# avrcp_m_1_2.net
KiCad netlist of a schematic drawn in EAGLE
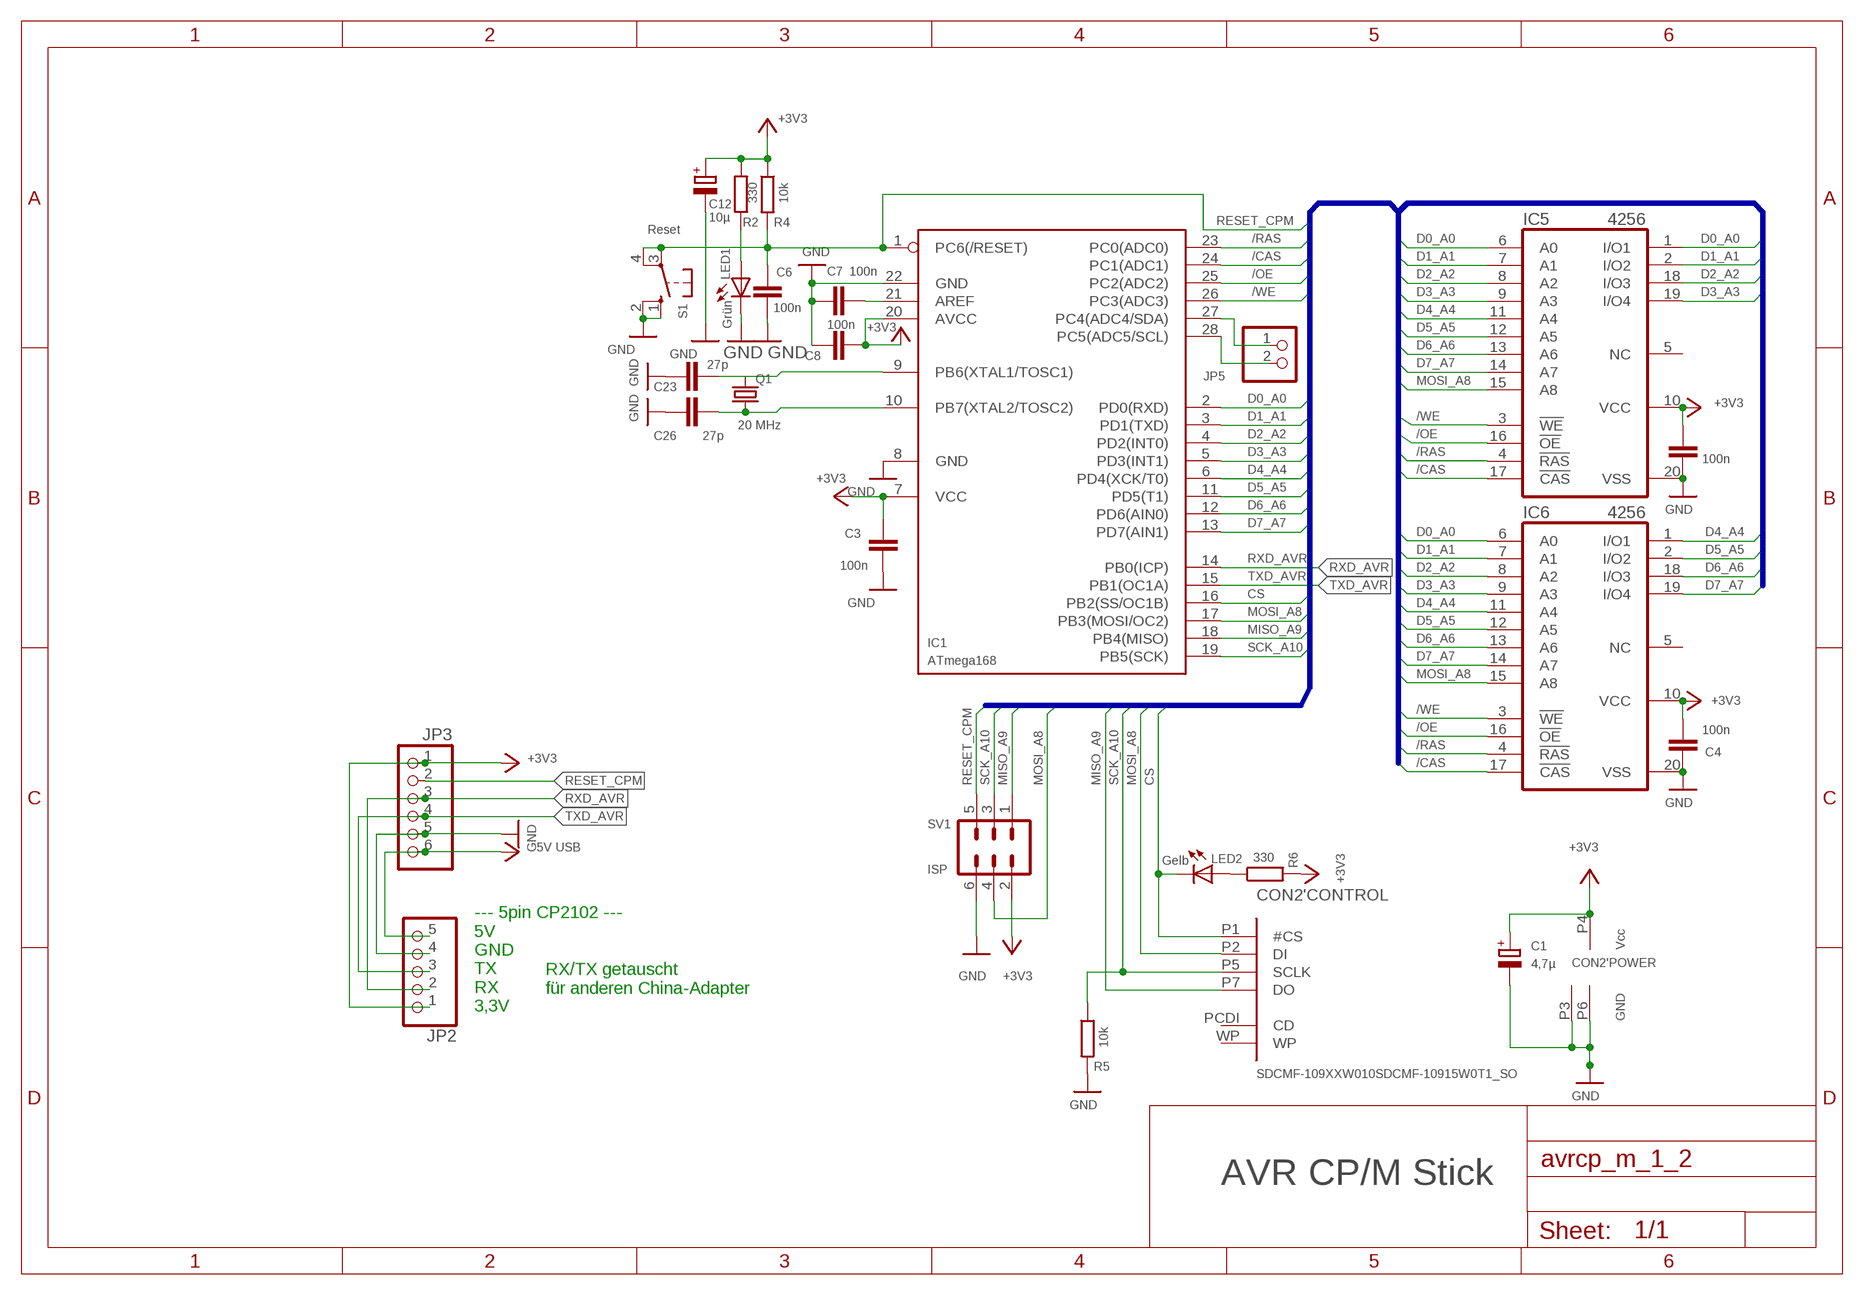
[diagram p0: schematic, sheet 1]

(export (version "E")
  (design (tool "Eeschema 10.0.6"))
  (components
    (comp (ref "C1")
      (value "4,7µ")
      (footprint "eagle-import:E2-4")
      (libsource (lib "eagle-import") (part "CPOL-EUE2-4"))
    )
    (comp (ref "C3")
      (value "100n")
      (footprint "eagle-import:C025-024X044")
      (libsource (lib "eagle-import") (part "C-EU025-024X044"))
    )
    (comp (ref "C4")
      (value "100n")
      (footprint "eagle-import:C025-024X044")
      (libsource (lib "eagle-import") (part "C-EU025-024X044"))
    )
    (comp (ref "C6")
      (value "100n")
      (footprint "eagle-import:C025-024X044")
      (libsource (lib "eagle-import") (part "C-EU025-024X044"))
    )
    (comp (ref "C7")
      (value "100n")
      (footprint "eagle-import:C025-024X044")
      (libsource (lib "eagle-import") (part "C-EU025-024X044"))
    )
    (comp (ref "C8")
      (value "100n")
      (footprint "eagle-import:C025-024X044")
      (libsource (lib "eagle-import") (part "C-EU025-024X044"))
    )
    (comp (ref "C12")
      (value "10µ")
      (footprint "eagle-import:E2-4")
      (libsource (lib "eagle-import") (part "CPOL-EUE2-4"))
    )
    (comp (ref "C15")
      (value "100n")
      (footprint "eagle-import:C025-024X044")
      (libsource (lib "eagle-import") (part "C-EU025-024X044"))
    )
    (comp (ref "C23")
      (value "27p")
      (footprint "eagle-import:C025-024X044")
      (libsource (lib "eagle-import") (part "C-EU025-024X044"))
    )
    (comp (ref "C26")
      (value "27p")
      (footprint "eagle-import:C025-024X044")
      (libsource (lib "eagle-import") (part "C-EU025-024X044"))
    )
    (comp (ref "CON2")
      (value "SDCMF-109XXW010SDCMF-10915W0T1_SO")
      (footprint "eagle-import:SDCMF-10915W0T1")
      (libsource (lib "eagle-import") (part "SDCMF-109XXW010SDCMF-10915W0T1_SO"))
    )
    (comp (ref "IC1")
      (value "ATmega168")
      (footprint "eagle-import:DIL28-3")
      (libsource (lib "eagle-import") (part "MEGA8-P"))
    )
    (comp (ref "IC5")
      (value "4256")
      (footprint "eagle-import:DIL20")
      (libsource (lib "eagle-import") (part "514256ALP"))
    )
    (comp (ref "IC6")
      (value "4256")
      (footprint "eagle-import:DIL20")
      (libsource (lib "eagle-import") (part "514256ALP"))
    )
    (comp (ref "JP2")
      (value "PINHD-1X5")
      (footprint "eagle-import:1X05")
      (libsource (lib "eagle-import") (part "PINHD-1X5"))
    )
    (comp (ref "JP3")
      (value "PINHD-1X6")
      (footprint "eagle-import:1X06")
      (libsource (lib "eagle-import") (part "PINHD-1X6"))
    )
    (comp (ref "JP5")
      (value "PINHD-1X2")
      (footprint "eagle-import:1X02")
      (libsource (lib "eagle-import") (part "PINHD-1X2"))
    )
    (comp (ref "LED1")
      (value "Grün")
      (footprint "eagle-import:LED3MM")
      (libsource (lib "eagle-import") (part "LED3MM"))
    )
    (comp (ref "LED2")
      (value "Gelb")
      (footprint "eagle-import:LED3MM")
      (libsource (lib "eagle-import") (part "LED3MM"))
    )
    (comp (ref "Q1")
      (value "20 MHz")
      (footprint "eagle-import:HC49_S")
      (libsource (lib "eagle-import") (part "CRYSTALHC49S"))
    )
    (comp (ref "R2")
      (value "330")
      (footprint "eagle-import:0207_7")
      (libsource (lib "eagle-import") (part "R-EU_0207/7"))
    )
    (comp (ref "R4")
      (value "10k")
      (footprint "eagle-import:0207_7")
      (libsource (lib "eagle-import") (part "R-EU_0207/7"))
    )
    (comp (ref "R5")
      (value "10k")
      (footprint "eagle-import:0204_7")
      (libsource (lib "eagle-import") (part "R-EU_0204/7"))
    )
    (comp (ref "R6")
      (value "330")
      (footprint "eagle-import:0204_7")
      (libsource (lib "eagle-import") (part "R-EU_0204/7"))
    )
    (comp (ref "S1")
      (value "Reset")
      (footprint "eagle-import:B3F-10XX")
      (libsource (lib "eagle-import") (part "10-XX"))
    )
    (comp (ref "SV1")
      (value "ISP")
      (footprint "eagle-import:ML6")
      (libsource (lib "eagle-import") (part "ML6"))
    )
  )
  (nets
    (net (code "1") (name "+3V3") (class "Default")
      (node (ref "C1") (pin "+") (pinfunction "+_+") (pintype "passive"))
      (node (ref "C12") (pin "+") (pinfunction "+_+") (pintype "passive"))
      (node (ref "C15") (pin "2") (pinfunction "2_2") (pintype "passive"))
      (node (ref "C3") (pin "1") (pinfunction "1_1") (pintype "passive"))
      (node (ref "C4") (pin "2") (pinfunction "2_2") (pintype "passive"))
      (node (ref "C8") (pin "1") (pinfunction "1_1") (pintype "passive"))
      (node (ref "CON2") (pin "P4") (pinfunction "VCC_P4") (pintype "power_in"))
      (node (ref "IC1") (pin "20") (pinfunction "AVCC_20") (pintype "power_in"))
      (node (ref "IC1") (pin "7") (pinfunction "VCC_7") (pintype "power_in"))
      (node (ref "IC5") (pin "10") (pinfunction "VCC_10") (pintype "power_in"))
      (node (ref "IC6") (pin "10") (pinfunction "VCC_10") (pintype "power_in"))
      (node (ref "JP2") (pin "1") (pinfunction "1_1") (pintype "passive"))
      (node (ref "JP3") (pin "1") (pinfunction "1_1") (pintype "passive"))
      (node (ref "R2") (pin "2") (pinfunction "2_2") (pintype "passive"))
      (node (ref "R4") (pin "1") (pinfunction "1_1") (pintype "passive"))
      (node (ref "R6") (pin "2") (pinfunction "2_2") (pintype "passive"))
      (node (ref "SV1") (pin "2") (pinfunction "2_2") (pintype "passive"))
    )
    (net (code "2") (name "/CS") (class "Default")
      (node (ref "CON2") (pin "P1") (pinfunction "#CS_P1") (pintype "input"))
      (node (ref "IC1") (pin "16") (pinfunction "PB2(SS/OC1B)_16") (pintype "bidirectional"))
      (node (ref "LED2") (pin "K") (pinfunction "C_K") (pintype "passive"))
    )
    (net (code "3") (name "/D0_A0") (class "Default")
      (node (ref "IC1") (pin "2") (pinfunction "PD0(RXD)_2") (pintype "bidirectional"))
      (node (ref "IC5") (pin "1") (pinfunction "I/O1_1") (pintype "bidirectional"))
      (node (ref "IC5") (pin "6") (pinfunction "A0_6") (pintype "input"))
      (node (ref "IC6") (pin "6") (pinfunction "A0_6") (pintype "input"))
    )
    (net (code "4") (name "/D1_A1") (class "Default")
      (node (ref "IC1") (pin "3") (pinfunction "PD1(TXD)_3") (pintype "bidirectional"))
      (node (ref "IC5") (pin "2") (pinfunction "I/O2_2") (pintype "bidirectional"))
      (node (ref "IC5") (pin "7") (pinfunction "A1_7") (pintype "input"))
      (node (ref "IC6") (pin "7") (pinfunction "A1_7") (pintype "input"))
    )
    (net (code "5") (name "/D2_A2") (class "Default")
      (node (ref "IC1") (pin "4") (pinfunction "PD2(INT0)_4") (pintype "bidirectional"))
      (node (ref "IC5") (pin "18") (pinfunction "I/O3_18") (pintype "bidirectional"))
      (node (ref "IC5") (pin "8") (pinfunction "A2_8") (pintype "input"))
      (node (ref "IC6") (pin "8") (pinfunction "A2_8") (pintype "input"))
    )
    (net (code "6") (name "/D3_A3") (class "Default")
      (node (ref "IC1") (pin "5") (pinfunction "PD3(INT1)_5") (pintype "bidirectional"))
      (node (ref "IC5") (pin "19") (pinfunction "I/O4_19") (pintype "bidirectional"))
      (node (ref "IC5") (pin "9") (pinfunction "A3_9") (pintype "input"))
      (node (ref "IC6") (pin "9") (pinfunction "A3_9") (pintype "input"))
    )
    (net (code "7") (name "/D4_A4") (class "Default")
      (node (ref "IC1") (pin "6") (pinfunction "PD4(XCK/T0)_6") (pintype "bidirectional"))
      (node (ref "IC5") (pin "11") (pinfunction "A4_11") (pintype "input"))
      (node (ref "IC6") (pin "1") (pinfunction "I/O1_1") (pintype "bidirectional"))
      (node (ref "IC6") (pin "11") (pinfunction "A4_11") (pintype "input"))
    )
    (net (code "8") (name "/D5_A5") (class "Default")
      (node (ref "IC1") (pin "11") (pinfunction "PD5(T1)_11") (pintype "bidirectional"))
      (node (ref "IC5") (pin "12") (pinfunction "A5_12") (pintype "input"))
      (node (ref "IC6") (pin "12") (pinfunction "A5_12") (pintype "input"))
      (node (ref "IC6") (pin "2") (pinfunction "I/O2_2") (pintype "bidirectional"))
    )
    (net (code "9") (name "/D6_A6") (class "Default")
      (node (ref "IC1") (pin "12") (pinfunction "PD6(AIN0)_12") (pintype "bidirectional"))
      (node (ref "IC5") (pin "13") (pinfunction "A6_13") (pintype "input"))
      (node (ref "IC6") (pin "13") (pinfunction "A6_13") (pintype "input"))
      (node (ref "IC6") (pin "18") (pinfunction "I/O3_18") (pintype "bidirectional"))
    )
    (net (code "10") (name "/D7_A7") (class "Default")
      (node (ref "IC1") (pin "13") (pinfunction "PD7(AIN1)_13") (pintype "bidirectional"))
      (node (ref "IC5") (pin "14") (pinfunction "A7_14") (pintype "input"))
      (node (ref "IC6") (pin "14") (pinfunction "A7_14") (pintype "input"))
      (node (ref "IC6") (pin "19") (pinfunction "I/O4_19") (pintype "bidirectional"))
    )
    (net (code "11") (name "/MISO_A9") (class "Default")
      (node (ref "CON2") (pin "P7") (pinfunction "DO_P7") (pintype "output"))
      (node (ref "IC1") (pin "18") (pinfunction "PB4(MISO)_18") (pintype "bidirectional"))
      (node (ref "SV1") (pin "1") (pinfunction "1_1") (pintype "passive"))
    )
    (net (code "12") (name "/MOSI_A8") (class "Default")
      (node (ref "CON2") (pin "P2") (pinfunction "DI_P2") (pintype "input"))
      (node (ref "IC1") (pin "17") (pinfunction "PB3(MOSI/OC2)_17") (pintype "bidirectional"))
      (node (ref "IC5") (pin "15") (pinfunction "A8_15") (pintype "input"))
      (node (ref "IC6") (pin "15") (pinfunction "A8_15") (pintype "input"))
      (node (ref "SV1") (pin "4") (pinfunction "4_4") (pintype "passive"))
    )
    (net (code "13") (name "/SCK_A10") (class "Default")
      (node (ref "CON2") (pin "P5") (pinfunction "SCLK_P5") (pintype "input"))
      (node (ref "IC1") (pin "19") (pinfunction "PB5(SCK)_19") (pintype "bidirectional"))
      (node (ref "R5") (pin "1") (pinfunction "1_1") (pintype "passive"))
      (node (ref "SV1") (pin "3") (pinfunction "3_3") (pintype "passive"))
    )
    (net (code "14") (name "/{slash}CAS") (class "Default")
      (node (ref "IC1") (pin "24") (pinfunction "PC1(ADC1)_24") (pintype "bidirectional"))
      (node (ref "IC5") (pin "17") (pinfunction "~{CAS}_17") (pintype "input"))
      (node (ref "IC6") (pin "17") (pinfunction "~{CAS}_17") (pintype "input"))
    )
    (net (code "15") (name "/{slash}OE") (class "Default")
      (node (ref "IC1") (pin "25") (pinfunction "PC2(ADC2)_25") (pintype "bidirectional"))
      (node (ref "IC5") (pin "16") (pinfunction "~{OE}_16") (pintype "input"))
      (node (ref "IC6") (pin "16") (pinfunction "~{OE}_16") (pintype "input"))
    )
    (net (code "16") (name "/{slash}RAS") (class "Default")
      (node (ref "IC1") (pin "23") (pinfunction "PC0(ADC0)_23") (pintype "bidirectional"))
      (node (ref "IC5") (pin "4") (pinfunction "~{RAS}_4") (pintype "input"))
      (node (ref "IC6") (pin "4") (pinfunction "~{RAS}_4") (pintype "input"))
    )
    (net (code "17") (name "/{slash}WE") (class "Default")
      (node (ref "IC1") (pin "26") (pinfunction "PC3(ADC3)_26") (pintype "bidirectional"))
      (node (ref "IC5") (pin "3") (pinfunction "~{WE}_3") (pintype "input"))
      (node (ref "IC6") (pin "3") (pinfunction "~{WE}_3") (pintype "input"))
    )
    (net (code "18") (name "5V USB") (class "Default")
      (node (ref "JP2") (pin "5") (pinfunction "5_5") (pintype "passive"))
      (node (ref "JP3") (pin "6") (pinfunction "6_6") (pintype "passive"))
    )
    (net (code "19") (name "GND") (class "Default")
      (node (ref "C1") (pin "-") (pinfunction "-_-") (pintype "passive"))
      (node (ref "C12") (pin "-") (pinfunction "-_-") (pintype "passive"))
      (node (ref "C15") (pin "1") (pinfunction "1_1") (pintype "passive"))
      (node (ref "C23") (pin "2") (pinfunction "2_2") (pintype "passive"))
      (node (ref "C26") (pin "2") (pinfunction "2_2") (pintype "passive"))
      (node (ref "C3") (pin "2") (pinfunction "2_2") (pintype "passive"))
      (node (ref "C4") (pin "1") (pinfunction "1_1") (pintype "passive"))
      (node (ref "C6") (pin "1") (pinfunction "1_1") (pintype "passive"))
      (node (ref "C7") (pin "2") (pinfunction "2_2") (pintype "passive"))
      (node (ref "C8") (pin "2") (pinfunction "2_2") (pintype "passive"))
      (node (ref "CON2") (pin "P3") (pinfunction "GND_P3") (pintype "power_in"))
      (node (ref "CON2") (pin "P6") (pinfunction "GND_P6") (pintype "power_in"))
      (node (ref "IC1") (pin "22") (pinfunction "GND_22") (pintype "power_in"))
      (node (ref "IC1") (pin "8") (pinfunction "GND_8") (pintype "power_in"))
      (node (ref "IC5") (pin "20") (pinfunction "VSS_20") (pintype "power_in"))
      (node (ref "IC6") (pin "20") (pinfunction "VSS_20") (pintype "power_in"))
      (node (ref "JP2") (pin "4") (pinfunction "4_4") (pintype "passive"))
      (node (ref "JP3") (pin "5") (pinfunction "5_5") (pintype "passive"))
      (node (ref "LED1") (pin "K") (pinfunction "C_K") (pintype "passive"))
      (node (ref "R5") (pin "2") (pinfunction "2_2") (pintype "passive"))
      (node (ref "S1") (pin "1") (pinfunction "S_1") (pintype "passive"))
      (node (ref "S1") (pin "2") (pinfunction "S1_2") (pintype "passive"))
      (node (ref "SV1") (pin "6") (pinfunction "6_6") (pintype "passive"))
    )
    (net (code "20") (name "Net-(IC1-AREF)") (class "Default")
      (node (ref "C7") (pin "1") (pinfunction "1_1") (pintype "passive"))
      (node (ref "IC1") (pin "21") (pinfunction "AREF_21") (pintype "passive"))
    )
    (net (code "21") (name "Net-(IC1-PB6(XTAL1{slash}TOSC1))") (class "Default")
      (node (ref "C23") (pin "1") (pinfunction "1_1") (pintype "passive"))
      (node (ref "IC1") (pin "9") (pinfunction "PB6(XTAL1/TOSC1)_9") (pintype "bidirectional"))
      (node (ref "Q1") (pin "2") (pinfunction "2_2") (pintype "passive"))
    )
    (net (code "22") (name "Net-(IC1-PB7(XTAL2{slash}TOSC2))") (class "Default")
      (node (ref "C26") (pin "1") (pinfunction "1_1") (pintype "passive"))
      (node (ref "IC1") (pin "10") (pinfunction "PB7(XTAL2/TOSC2)_10") (pintype "bidirectional"))
      (node (ref "Q1") (pin "1") (pinfunction "1_1") (pintype "passive"))
    )
    (net (code "23") (name "Net-(IC1-PC4(ADC4{slash}SDA))") (class "Default")
      (node (ref "IC1") (pin "27") (pinfunction "PC4(ADC4/SDA)_27") (pintype "bidirectional"))
      (node (ref "JP5") (pin "1") (pinfunction "1_1") (pintype "passive"))
    )
    (net (code "24") (name "Net-(IC1-PC5(ADC5{slash}SCL))") (class "Default")
      (node (ref "IC1") (pin "28") (pinfunction "PC5(ADC5/SCL)_28") (pintype "bidirectional"))
      (node (ref "JP5") (pin "2") (pinfunction "2_2") (pintype "passive"))
    )
    (net (code "25") (name "Net-(LED1-PadA)") (class "Default")
      (node (ref "LED1") (pin "A") (pinfunction "A_A") (pintype "passive"))
      (node (ref "R2") (pin "1") (pinfunction "1_1") (pintype "passive"))
    )
    (net (code "26") (name "Net-(LED2-PadA)") (class "Default")
      (node (ref "LED2") (pin "A") (pinfunction "A_A") (pintype "passive"))
      (node (ref "R6") (pin "1") (pinfunction "1_1") (pintype "passive"))
    )
    (net (code "27") (name "RESET_CPM") (class "Default")
      (node (ref "C6") (pin "2") (pinfunction "2_2") (pintype "passive"))
      (node (ref "IC1") (pin "1") (pinfunction "PC6(/RESET)_1") (pintype "bidirectional"))
      (node (ref "JP3") (pin "2") (pinfunction "2_2") (pintype "passive"))
      (node (ref "R4") (pin "2") (pinfunction "2_2") (pintype "passive"))
      (node (ref "S1") (pin "3") (pinfunction "P_3") (pintype "passive"))
      (node (ref "S1") (pin "4") (pinfunction "P1_4") (pintype "passive"))
      (node (ref "SV1") (pin "5") (pinfunction "5_5") (pintype "passive"))
    )
    (net (code "28") (name "RXD_AVR") (class "Default")
      (node (ref "IC1") (pin "14") (pinfunction "PB0(ICP)_14") (pintype "bidirectional"))
      (node (ref "JP2") (pin "2") (pinfunction "2_2") (pintype "passive"))
      (node (ref "JP3") (pin "3") (pinfunction "3_3") (pintype "passive"))
    )
    (net (code "29") (name "TXD_AVR") (class "Default")
      (node (ref "IC1") (pin "15") (pinfunction "PB1(OC1A)_15") (pintype "bidirectional"))
      (node (ref "JP2") (pin "3") (pinfunction "3_3") (pintype "passive"))
      (node (ref "JP3") (pin "4") (pinfunction "4_4") (pintype "passive"))
    )
    (net (code "30") (name "unconnected-(CON2-PadWP)") (class "Default")
      (node (ref "CON2") (pin "WP") (pinfunction "WP_WP") (pintype "open_collector"))
    )
    (net (code "31") (name "unconnected-(CON2A-CD-PadPCDI)") (class "Default")
      (node (ref "CON2") (pin "PCDI") (pinfunction "CD_PCDI") (pintype "open_collector"))
    )
    (net (code "32") (name "unconnected-(IC5-NC-Pad5)") (class "Default")
      (node (ref "IC5") (pin "5") (pinfunction "NC_5") (pintype "no_connect"))
    )
    (net (code "33") (name "unconnected-(IC6-NC-Pad5)") (class "Default")
      (node (ref "IC6") (pin "5") (pinfunction "NC_5") (pintype "no_connect"))
    )
  )
)
